# tl494module_1.net
KiCad netlist of a schematic drawn in EAGLE
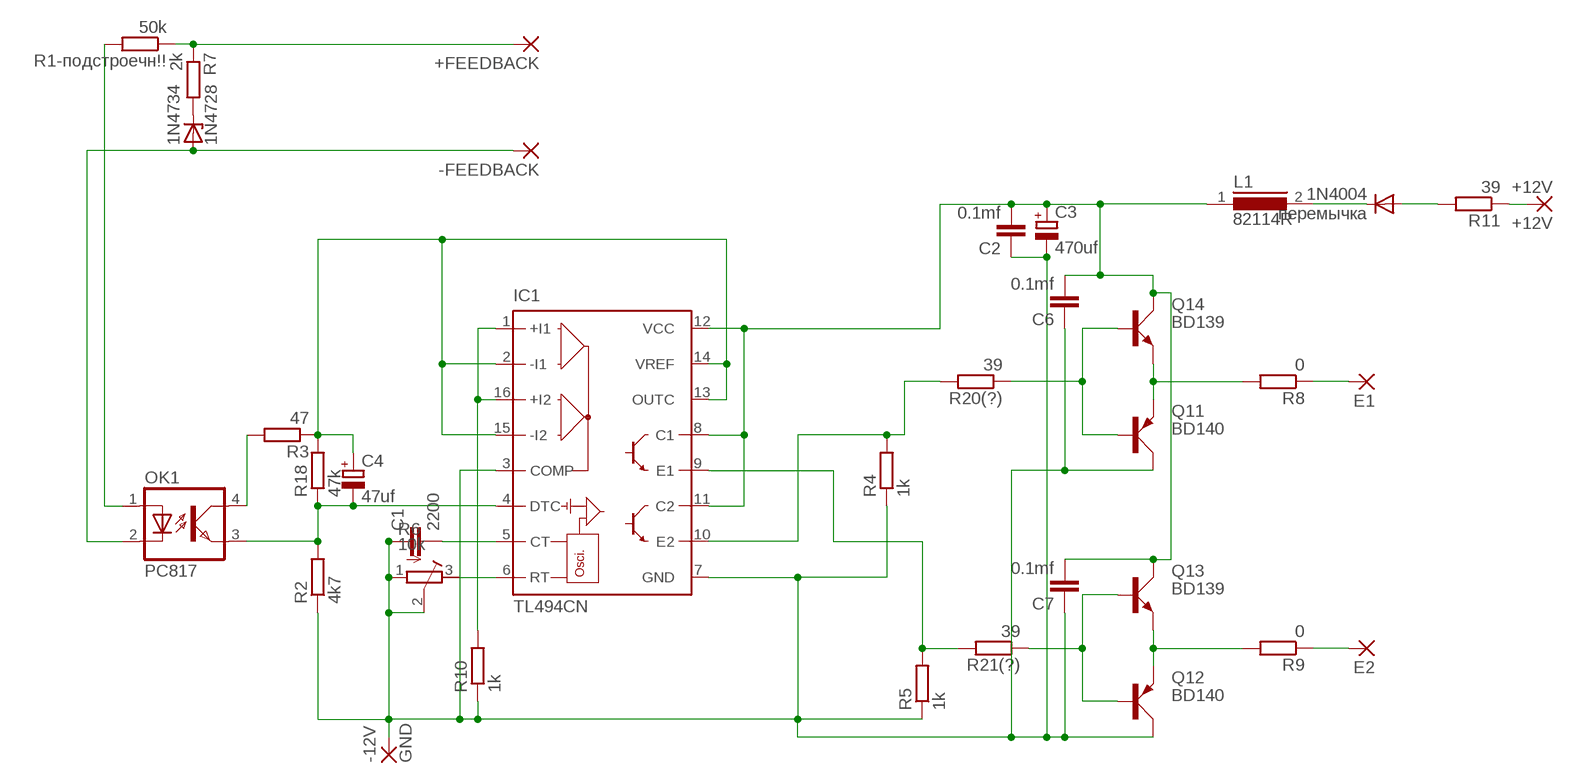
[diagram p0: schematic, sheet 1]

(export (version "E")
  (design (tool "Eeschema 10.0.6"))
  (components
    (comp (ref "+12V")
      (value "+12V")
      (footprint "eagle-import:3,81_1,1")
      (libsource (lib "eagle-import") (part "3,81/1,1"))
    )
    (comp (ref "+FEEDBACK")
      (value "3,81/1,1")
      (footprint "eagle-import:3,81_1,1")
      (libsource (lib "eagle-import") (part "3,81/1,1"))
    )
    (comp (ref "-12V")
      (value "GND")
      (footprint "eagle-import:3,81_1,1")
      (libsource (lib "eagle-import") (part "3,81/1,1"))
    )
    (comp (ref "-FEEDBACK")
      (value "3,81/1,1")
      (footprint "eagle-import:3,81_1,1")
      (libsource (lib "eagle-import") (part "3,81/1,1"))
    )
    (comp (ref "1N4734")
      (value "1N4728")
      (footprint "eagle-import:DO41Z10")
      (libsource (lib "eagle-import") (part "1N4728"))
    )
    (comp (ref "C1")
      (value "2200")
      (footprint "eagle-import:C050-025X075")
      (libsource (lib "eagle-import") (part "C-EU050-025X075"))
    )
    (comp (ref "C2")
      (value "0.1mf")
      (footprint "eagle-import:C050-025X075")
      (libsource (lib "eagle-import") (part "C-EU050-025X075"))
    )
    (comp (ref "C3")
      (value "470uf")
      (footprint "eagle-import:E2-4")
      (libsource (lib "eagle-import") (part "CPOL-EUE2-4"))
    )
    (comp (ref "C4")
      (value "47uf")
      (footprint "eagle-import:E2-4")
      (libsource (lib "eagle-import") (part "CPOL-EUE2-4"))
    )
    (comp (ref "C6")
      (value "0.1mf")
      (footprint "eagle-import:C050-025X075")
      (libsource (lib "eagle-import") (part "C-EU050-025X075"))
    )
    (comp (ref "C7")
      (value "0.1mf")
      (footprint "eagle-import:C050-025X075")
      (libsource (lib "eagle-import") (part "C-EU050-025X075"))
    )
    (comp (ref "E1")
      (value "3,81/1,1")
      (footprint "eagle-import:3,81_1,1")
      (libsource (lib "eagle-import") (part "3,81/1,1"))
    )
    (comp (ref "E2")
      (value "3,81/1,1")
      (footprint "eagle-import:3,81_1,1")
      (libsource (lib "eagle-import") (part "3,81/1,1"))
    )
    (comp (ref "IC1")
      (value "TL494CN")
      (footprint "eagle-import:DIL16")
      (libsource (lib "eagle-import") (part "TL494NC"))
    )
    (comp (ref "L1")
      (value "82114R")
      (footprint "eagle-import:82114R")
      (libsource (lib "eagle-import") (part "82114R"))
    )
    (comp (ref "OK1")
      (value "PC817")
      (footprint "eagle-import:DIL04")
      (fields (field (name "MPN") "PC817X4J000F"))
      (libsource (lib "eagle-import") (part "PC817"))
    )
    (comp (ref "Q11")
      (value "BD140")
      (footprint "eagle-import:TO126AV")
      (libsource (lib "eagle-import") (part "BD140"))
    )
    (comp (ref "Q12")
      (value "BD140")
      (footprint "eagle-import:TO126AV")
      (libsource (lib "eagle-import") (part "BD140"))
    )
    (comp (ref "Q13")
      (value "BD139")
      (footprint "eagle-import:TO126AV")
      (libsource (lib "eagle-import") (part "BD139"))
    )
    (comp (ref "Q14")
      (value "BD139")
      (footprint "eagle-import:TO126AV")
      (libsource (lib "eagle-import") (part "BD139"))
    )
    (comp (ref "R1-подстроечн!!")
      (value "50k")
      (footprint "eagle-import:0204_7")
      (libsource (lib "eagle-import") (part "R-EU_0204/7"))
    )
    (comp (ref "R2")
      (value "4k7")
      (footprint "eagle-import:0204_7")
      (libsource (lib "eagle-import") (part "R-EU_0204/7"))
    )
    (comp (ref "R3")
      (value "47")
      (footprint "eagle-import:0204_7")
      (libsource (lib "eagle-import") (part "R-EU_0204/7"))
    )
    (comp (ref "R4")
      (value "1k")
      (footprint "eagle-import:0204_7")
      (libsource (lib "eagle-import") (part "R-EU_0204/7"))
    )
    (comp (ref "R5")
      (value "1k")
      (footprint "eagle-import:0204_7")
      (libsource (lib "eagle-import") (part "R-EU_0204/7"))
    )
    (comp (ref "R6")
      (value "10k")
      (footprint "eagle-import:RTRIM3296W")
      (libsource (lib "eagle-import") (part "R-TRIMM3296W"))
    )
    (comp (ref "R7")
      (value "2k")
      (footprint "eagle-import:0204_7")
      (libsource (lib "eagle-import") (part "R-EU_0204/7"))
    )
    (comp (ref "R8")
      (value "0")
      (footprint "eagle-import:0204_7")
      (libsource (lib "eagle-import") (part "R-EU_0204/7"))
    )
    (comp (ref "R9")
      (value "0")
      (footprint "eagle-import:0204_7")
      (libsource (lib "eagle-import") (part "R-EU_0204/7"))
    )
    (comp (ref "R10")
      (value "1k")
      (footprint "eagle-import:0204_7")
      (libsource (lib "eagle-import") (part "R-EU_0204/7"))
    )
    (comp (ref "R11")
      (value "39")
      (footprint "eagle-import:0204_7")
      (libsource (lib "eagle-import") (part "R-EU_0204/7"))
    )
    (comp (ref "R18")
      (value "47k")
      (footprint "eagle-import:0204_7")
      (libsource (lib "eagle-import") (part "R-EU_0204/7"))
    )
    (comp (ref "R20(?)")
      (value "39")
      (footprint "eagle-import:0204_7")
      (libsource (lib "eagle-import") (part "R-EU_0204/7"))
    )
    (comp (ref "R21(?)")
      (value "39")
      (footprint "eagle-import:0204_7")
      (libsource (lib "eagle-import") (part "R-EU_0204/7"))
    )
    (comp (ref "перемычка")
      (value "1N4004")
      (footprint "eagle-import:DO41-10")
      (libsource (lib "eagle-import") (part "1N4004"))
    )
  )
  (nets
    (net (code "1") (name "Net-(+12V-P)") (class "Default")
      (node (ref "+12V") (pin "1") (pinfunction "P_1") (pintype "passive"))
      (node (ref "R11") (pin "1") (pinfunction "1_1") (pintype "passive"))
    )
    (net (code "2") (name "Net-(+FEEDBACK-P)") (class "Default")
      (node (ref "+FEEDBACK") (pin "1") (pinfunction "P_1") (pintype "passive"))
      (node (ref "R1-подстроечн!!") (pin "1") (pinfunction "1_1") (pintype "passive"))
      (node (ref "R7") (pin "1") (pinfunction "1_1") (pintype "passive"))
    )
    (net (code "3") (name "Net-(-12V-P)") (class "Default")
      (node (ref "-12V") (pin "1") (pinfunction "P_1") (pintype "passive"))
      (node (ref "C1") (pin "1") (pinfunction "1_1") (pintype "passive"))
      (node (ref "C2") (pin "1") (pinfunction "1_1") (pintype "passive"))
      (node (ref "C3") (pin "-") (pinfunction "-_-") (pintype "passive"))
      (node (ref "C6") (pin "1") (pinfunction "1_1") (pintype "passive"))
      (node (ref "C7") (pin "1") (pinfunction "1_1") (pintype "passive"))
      (node (ref "IC1") (pin "3") (pinfunction "COMP_3") (pintype "passive"))
      (node (ref "IC1") (pin "7") (pinfunction "GND_7") (pintype "power_in"))
      (node (ref "Q11") (pin "C") (pinfunction "C_C") (pintype "passive"))
      (node (ref "Q12") (pin "C") (pinfunction "C_C") (pintype "passive"))
      (node (ref "R10") (pin "1") (pinfunction "1_1") (pintype "passive"))
      (node (ref "R2") (pin "1") (pinfunction "1_1") (pintype "passive"))
      (node (ref "R4") (pin "1") (pinfunction "1_1") (pintype "passive"))
      (node (ref "R5") (pin "1") (pinfunction "1_1") (pintype "passive"))
      (node (ref "R6") (pin "1") (pinfunction "A_1") (pintype "passive"))
      (node (ref "R6") (pin "2") (pinfunction "S_2") (pintype "passive"))
    )
    (net (code "4") (name "Net-(-FEEDBACK-P)") (class "Default")
      (node (ref "-FEEDBACK") (pin "1") (pinfunction "P_1") (pintype "passive"))
      (node (ref "1N4734") (pin "A") (pinfunction "A_A") (pintype "passive"))
      (node (ref "OK1") (pin "2") (pinfunction "C_2") (pintype "passive"))
    )
    (net (code "5") (name "Net-(1N4734-PadC)") (class "Default")
      (node (ref "1N4734") (pin "C") (pinfunction "C_C") (pintype "passive"))
      (node (ref "R7") (pin "2") (pinfunction "2_2") (pintype "passive"))
    )
    (net (code "6") (name "Net-(E1-P)") (class "Default")
      (node (ref "E1") (pin "1") (pinfunction "P_1") (pintype "passive"))
      (node (ref "R8") (pin "1") (pinfunction "1_1") (pintype "passive"))
    )
    (net (code "7") (name "Net-(E2-P)") (class "Default")
      (node (ref "E2") (pin "1") (pinfunction "P_1") (pintype "passive"))
      (node (ref "R9") (pin "1") (pinfunction "1_1") (pintype "passive"))
    )
    (net (code "8") (name "Net-(IC1-+I1)") (class "Default")
      (node (ref "IC1") (pin "1") (pinfunction "+I1_1") (pintype "input"))
      (node (ref "IC1") (pin "16") (pinfunction "+I2_16") (pintype "input"))
      (node (ref "R10") (pin "2") (pinfunction "2_2") (pintype "passive"))
    )
    (net (code "9") (name "Net-(IC1--I1)") (class "Default")
      (node (ref "C4") (pin "+") (pinfunction "+_+") (pintype "passive"))
      (node (ref "IC1") (pin "13") (pinfunction "OUTC_13") (pintype "output"))
      (node (ref "IC1") (pin "14") (pinfunction "VREF_14") (pintype "input"))
      (node (ref "IC1") (pin "15") (pinfunction "-I2_15") (pintype "input"))
      (node (ref "IC1") (pin "2") (pinfunction "-I1_2") (pintype "input"))
      (node (ref "R18") (pin "2") (pinfunction "2_2") (pintype "passive"))
      (node (ref "R3") (pin "1") (pinfunction "1_1") (pintype "passive"))
    )
    (net (code "10") (name "Net-(IC1-C1)") (class "Default")
      (node (ref "C2") (pin "2") (pinfunction "2_2") (pintype "passive"))
      (node (ref "C3") (pin "+") (pinfunction "+_+") (pintype "passive"))
      (node (ref "C6") (pin "2") (pinfunction "2_2") (pintype "passive"))
      (node (ref "C7") (pin "2") (pinfunction "2_2") (pintype "passive"))
      (node (ref "IC1") (pin "11") (pinfunction "C2_11") (pintype "passive"))
      (node (ref "IC1") (pin "12") (pinfunction "VCC_12") (pintype "power_in"))
      (node (ref "IC1") (pin "8") (pinfunction "C1_8") (pintype "passive"))
      (node (ref "L1") (pin "1") (pinfunction "1_1") (pintype "passive"))
      (node (ref "Q13") (pin "C") (pinfunction "C_C") (pintype "passive"))
      (node (ref "Q14") (pin "C") (pinfunction "C_C") (pintype "passive"))
    )
    (net (code "11") (name "Net-(IC1-CT)") (class "Default")
      (node (ref "C1") (pin "2") (pinfunction "2_2") (pintype "passive"))
      (node (ref "IC1") (pin "5") (pinfunction "CT_5") (pintype "input"))
    )
    (net (code "12") (name "Net-(IC1-DTC)") (class "Default")
      (node (ref "C4") (pin "-") (pinfunction "-_-") (pintype "passive"))
      (node (ref "IC1") (pin "4") (pinfunction "DTC_4") (pintype "input"))
      (node (ref "OK1") (pin "3") (pinfunction "EMIT_3") (pintype "passive"))
      (node (ref "R18") (pin "1") (pinfunction "1_1") (pintype "passive"))
      (node (ref "R2") (pin "2") (pinfunction "2_2") (pintype "passive"))
    )
    (net (code "13") (name "Net-(IC1-E1)") (class "Default")
      (node (ref "IC1") (pin "9") (pinfunction "E1_9") (pintype "passive"))
      (node (ref "R21(?)") (pin "2") (pinfunction "2_2") (pintype "passive"))
      (node (ref "R5") (pin "2") (pinfunction "2_2") (pintype "passive"))
    )
    (net (code "14") (name "Net-(IC1-E2)") (class "Default")
      (node (ref "IC1") (pin "10") (pinfunction "E2_10") (pintype "passive"))
      (node (ref "R20(?)") (pin "2") (pinfunction "2_2") (pintype "passive"))
      (node (ref "R4") (pin "2") (pinfunction "2_2") (pintype "passive"))
    )
    (net (code "15") (name "Net-(IC1-RT)") (class "Default")
      (node (ref "IC1") (pin "6") (pinfunction "RT_6") (pintype "input"))
      (node (ref "R6") (pin "3") (pinfunction "E_3") (pintype "passive"))
    )
    (net (code "16") (name "Net-(L1-Pad2)") (class "Default")
      (node (ref "L1") (pin "2") (pinfunction "2_2") (pintype "passive"))
      (node (ref "перемычка") (pin "C") (pinfunction "C_C") (pintype "passive"))
    )
    (net (code "17") (name "Net-(OK1-A)") (class "Default")
      (node (ref "OK1") (pin "1") (pinfunction "A_1") (pintype "passive"))
      (node (ref "R1-подстроечн!!") (pin "2") (pinfunction "2_2") (pintype "passive"))
    )
    (net (code "18") (name "Net-(OK1-COL)") (class "Default")
      (node (ref "OK1") (pin "4") (pinfunction "COL_4") (pintype "passive"))
      (node (ref "R3") (pin "2") (pinfunction "2_2") (pintype "passive"))
    )
    (net (code "19") (name "Net-(Q11-PadB)") (class "Default")
      (node (ref "Q11") (pin "B") (pinfunction "B_B") (pintype "passive"))
      (node (ref "Q14") (pin "B") (pinfunction "B_B") (pintype "passive"))
      (node (ref "R20(?)") (pin "1") (pinfunction "1_1") (pintype "passive"))
    )
    (net (code "20") (name "Net-(Q11-PadE)") (class "Default")
      (node (ref "Q11") (pin "E") (pinfunction "E_E") (pintype "passive"))
      (node (ref "Q14") (pin "E") (pinfunction "E_E") (pintype "passive"))
      (node (ref "R8") (pin "2") (pinfunction "2_2") (pintype "passive"))
    )
    (net (code "21") (name "Net-(Q12-PadB)") (class "Default")
      (node (ref "Q12") (pin "B") (pinfunction "B_B") (pintype "passive"))
      (node (ref "Q13") (pin "B") (pinfunction "B_B") (pintype "passive"))
      (node (ref "R21(?)") (pin "1") (pinfunction "1_1") (pintype "passive"))
    )
    (net (code "22") (name "Net-(Q12-PadE)") (class "Default")
      (node (ref "Q12") (pin "E") (pinfunction "E_E") (pintype "passive"))
      (node (ref "Q13") (pin "E") (pinfunction "E_E") (pintype "passive"))
      (node (ref "R9") (pin "2") (pinfunction "2_2") (pintype "passive"))
    )
    (net (code "23") (name "Net-(R11-Pad2)") (class "Default")
      (node (ref "R11") (pin "2") (pinfunction "2_2") (pintype "passive"))
      (node (ref "перемычка") (pin "A") (pinfunction "A_A") (pintype "passive"))
    )
  )
)
